# Modulo_Pisca_Vidros_SCH.net
KiCad netlist of a schematic drawn in Altium Designer
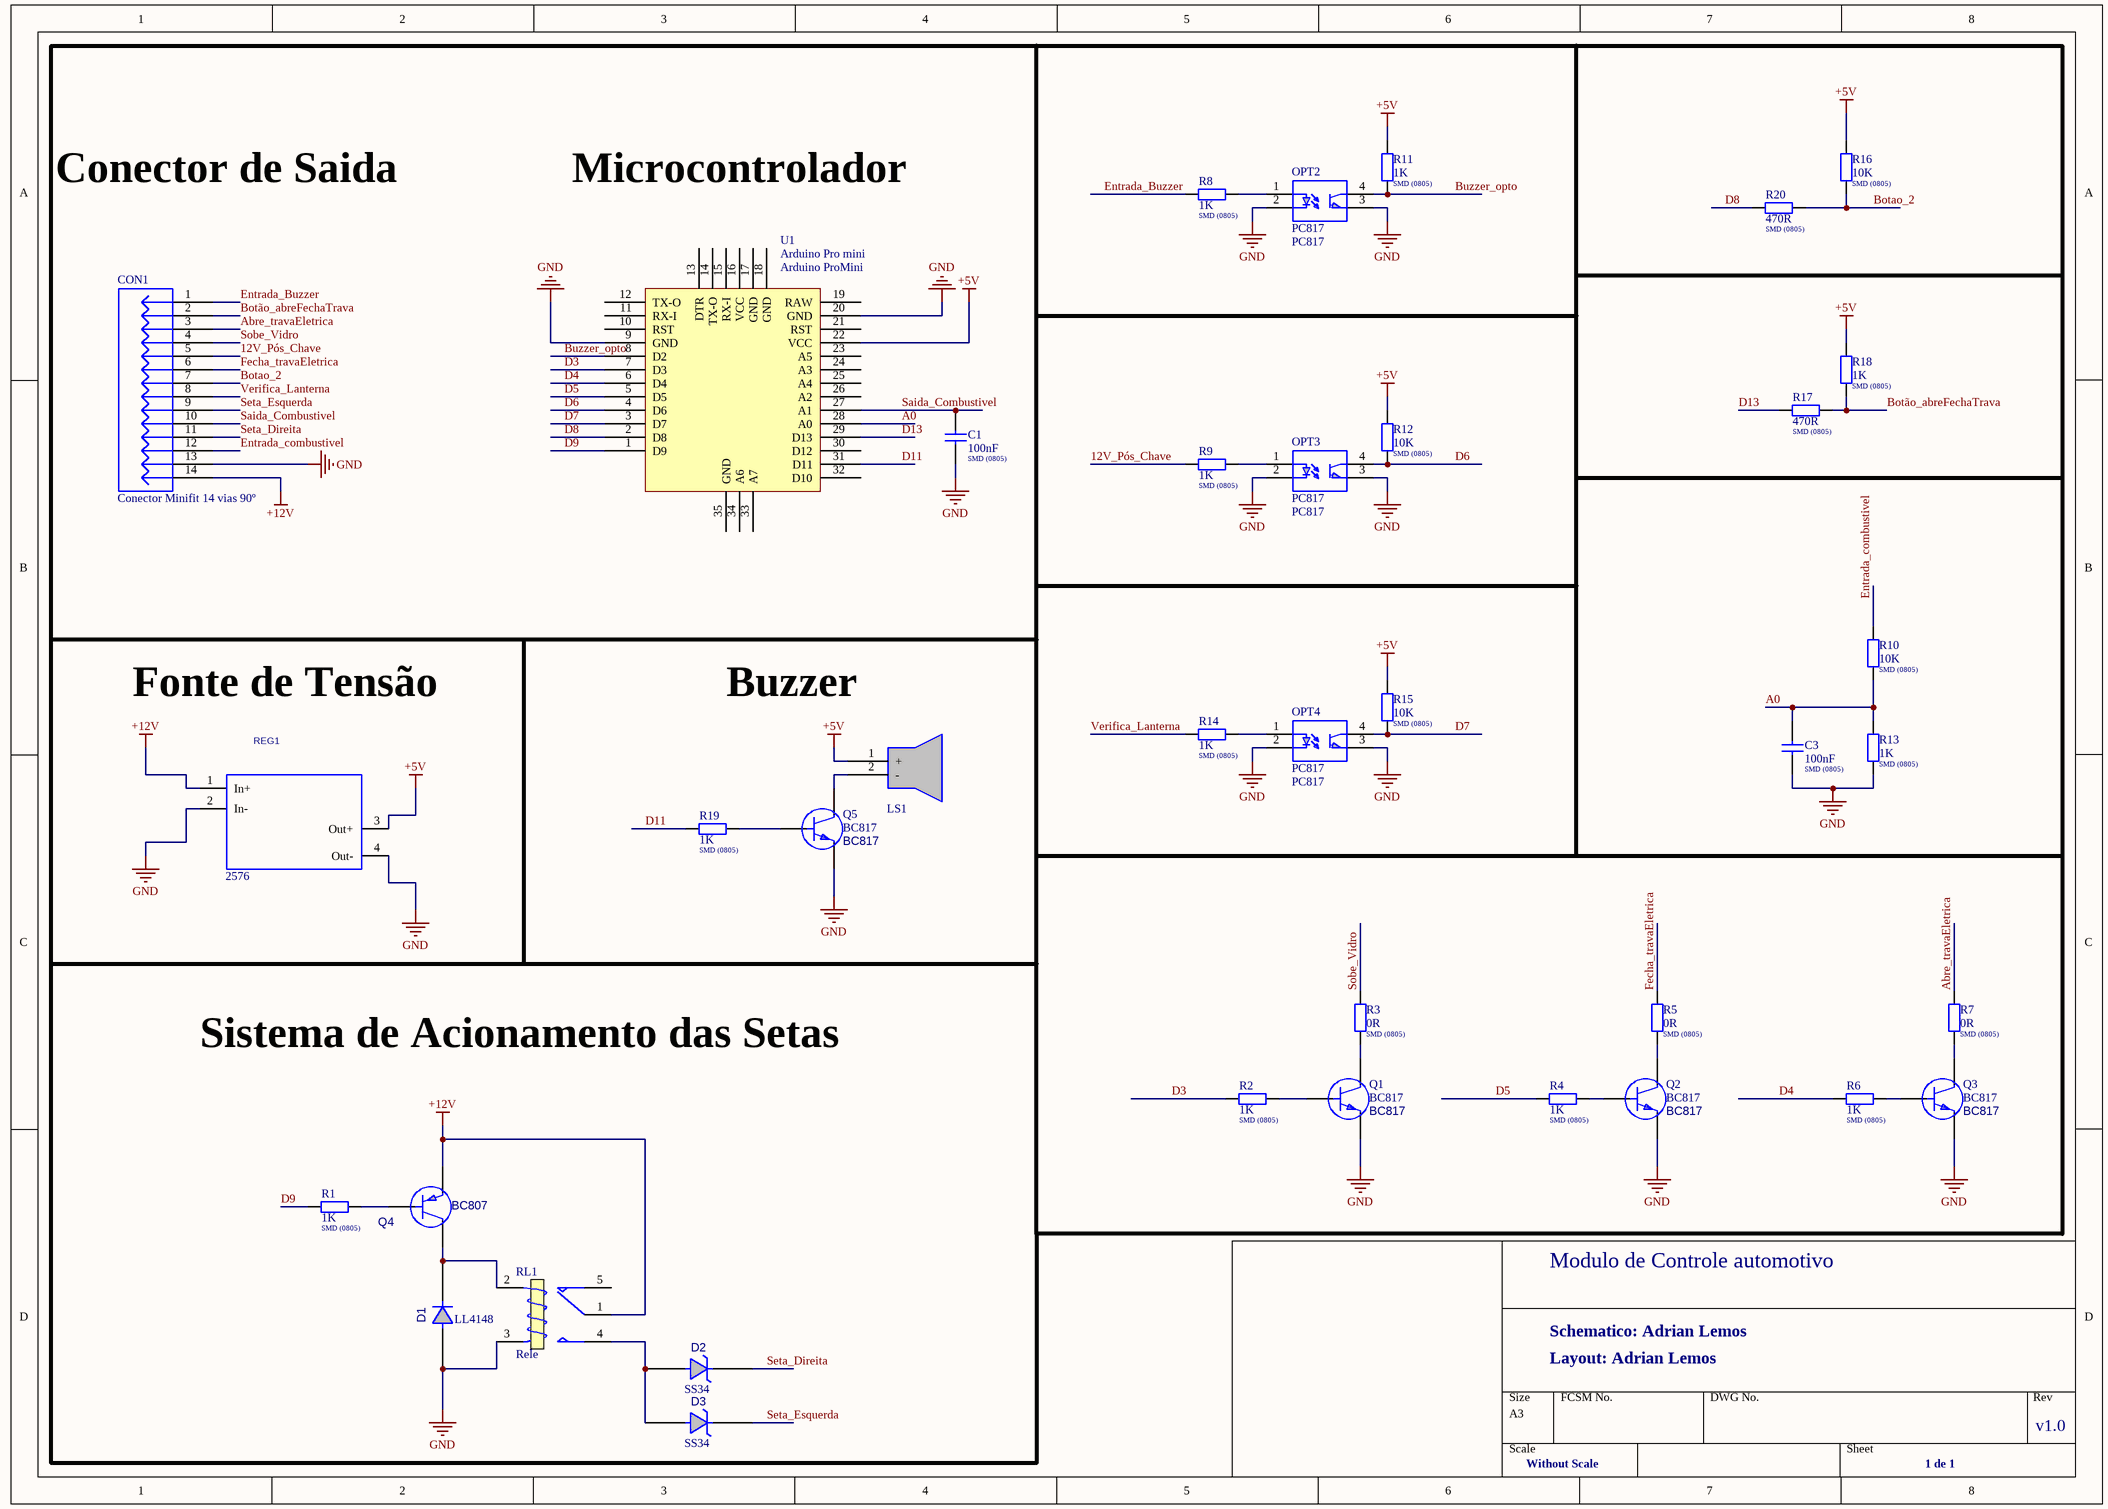
[diagram p0: Modulo_Pisca_Vidros_SCH.SchDoc]

(export (version "E")
  (design (tool "Eeschema 10.0.6"))
  (components
    (comp (ref "C1")
      (value "Capacitor SMD")
      (footprint "CAP_0805")
      (fields (field (name "VALOR") "100nF") (field (name "ENCAPSULAMENTO") "SMD (0805)"))
      (libsource (lib "Altium_Library_Brasil") (part "Capacitor SMD"))
    )
    (comp (ref "C3")
      (value "Capacitor SMD")
      (footprint "CAP_0805")
      (fields (field (name "VALOR") "100nF") (field (name "ENCAPSULAMENTO") "SMD (0805)"))
      (libsource (lib "Altium_Library_Brasil") (part "Capacitor SMD"))
    )
    (comp (ref "CON1")
      (value "Minifit_14vias_90º")
      (footprint "MFPL-14")
      (description "Minifit 14 vias 90º")
      (fields (field (name "DESCRI敲O") "Conector Minifit 14 vias 90º"))
      (libsource (lib "Altium_Library_Brasil") (part "Minifit_14vias_90º"))
    )
    (comp (ref "D1")
      (value "LL4148")
      (footprint "SOD80C MINIMELF")
      (description "Diodo LL4148 Melf")
      (fields (field (name "MODELO") "LL4148"))
      (libsource (lib "Altium_Library_Brasil") (part "LL4148"))
    )
    (comp (ref "D2")
      (value "SS34")
      (footprint "DO214AB")
      (description "DIODO-SCHOTTKY-SMD 3A 40V")
      (fields (field (name "MODELO") "SS34"))
      (libsource (lib "Altium_Library_Brasil") (part "SS34"))
    )
    (comp (ref "D3")
      (value "SS34")
      (footprint "DO214AB")
      (description "DIODO-SCHOTTKY-SMD 3A 40V")
      (fields (field (name "MODELO") "SS34"))
      (libsource (lib "Altium_Library_Brasil") (part "SS34"))
    )
    (comp (ref "LS1")
      (value "BUZZER")
      (footprint "Buzzer")
      (description "DC Buzzer")
      (libsource (lib "Altium_Library_Brasil") (part "BUZZER"))
    )
    (comp (ref "OPT2")
      (value "PC817")
      (footprint "DIP-4 SMD")
      (description "OptoAcoplador 4 terminais")
      (fields (field (name "MODELO") "PC817"))
      (libsource (lib "Altium_Library_Brasil") (part "PC817"))
    )
    (comp (ref "OPT3")
      (value "PC817")
      (footprint "DIP-4 SMD")
      (description "OptoAcoplador 4 terminais")
      (fields (field (name "MODELO") "PC817"))
      (libsource (lib "Altium_Library_Brasil") (part "PC817"))
    )
    (comp (ref "OPT4")
      (value "PC817")
      (footprint "DIP-4 SMD")
      (description "OptoAcoplador 4 terminais")
      (fields (field (name "MODELO") "PC817"))
      (libsource (lib "Altium_Library_Brasil") (part "PC817"))
    )
    (comp (ref "Q1")
      (value "BC817")
      (footprint "SOT23")
      (description "Transistor SMD NPN")
      (fields (field (name "MODELO") "BC817"))
      (libsource (lib "Altium_Library_Brasil") (part "BC817"))
    )
    (comp (ref "Q2")
      (value "BC817")
      (footprint "SOT23")
      (description "Transistor SMD NPN")
      (fields (field (name "MODELO") "BC817"))
      (libsource (lib "Altium_Library_Brasil") (part "BC817"))
    )
    (comp (ref "Q3")
      (value "BC817")
      (footprint "SOT23")
      (description "Transistor SMD NPN")
      (fields (field (name "MODELO") "BC817"))
      (libsource (lib "Altium_Library_Brasil") (part "BC817"))
    )
    (comp (ref "Q4")
      (value "BC807")
      (footprint "SOT23")
      (description "Transistor SMD PNP")
      (fields (field (name "MODELO") "BC807"))
      (libsource (lib "Altium_Library_Brasil") (part "BC807"))
    )
    (comp (ref "Q5")
      (value "BC817")
      (footprint "SOT23")
      (description "Transistor SMD NPN")
      (fields (field (name "MODELO") "BC817"))
      (libsource (lib "Altium_Library_Brasil") (part "BC817"))
    )
    (comp (ref "R1")
      (value "Resistor SMD")
      (footprint "RES_0805")
      (fields (field (name "VALOR") "1K") (field (name "ENCAPSULAMENTO") "SMD (0805)"))
      (libsource (lib "") (part "Resistor SMD_1"))
    )
    (comp (ref "R2")
      (value "Resistor SMD")
      (footprint "RES_0805")
      (fields (field (name "VALOR") "1K") (field (name "ENCAPSULAMENTO") "SMD (0805)"))
      (libsource (lib "") (part "Resistor SMD_1"))
    )
    (comp (ref "R3")
      (value "Resistor SMD")
      (footprint "RES_0805")
      (fields (field (name "VALOR") "0R") (field (name "ENCAPSULAMENTO") "SMD (0805)"))
      (libsource (lib "") (part "Resistor SMD_2"))
    )
    (comp (ref "R4")
      (value "Resistor SMD")
      (footprint "RES_0805")
      (fields (field (name "VALOR") "1K") (field (name "ENCAPSULAMENTO") "SMD (0805)"))
      (libsource (lib "") (part "Resistor SMD_1"))
    )
    (comp (ref "R5")
      (value "Resistor SMD")
      (footprint "RES_0805")
      (fields (field (name "VALOR") "0R") (field (name "ENCAPSULAMENTO") "SMD (0805)"))
      (libsource (lib "") (part "Resistor SMD_2"))
    )
    (comp (ref "R6")
      (value "Resistor SMD")
      (footprint "RES_0805")
      (fields (field (name "VALOR") "1K") (field (name "ENCAPSULAMENTO") "SMD (0805)"))
      (libsource (lib "") (part "Resistor SMD_1"))
    )
    (comp (ref "R7")
      (value "Resistor SMD")
      (footprint "RES_0805")
      (fields (field (name "VALOR") "0R") (field (name "ENCAPSULAMENTO") "SMD (0805)"))
      (libsource (lib "") (part "Resistor SMD_2"))
    )
    (comp (ref "R8")
      (value "Resistor SMD")
      (footprint "RES_0805")
      (fields (field (name "VALOR") "1K") (field (name "ENCAPSULAMENTO") "SMD (0805)"))
      (libsource (lib "Altium_Library_Brasil") (part "Resistor SMD"))
    )
    (comp (ref "R9")
      (value "Resistor SMD")
      (footprint "RES_0805")
      (fields (field (name "VALOR") "1K") (field (name "ENCAPSULAMENTO") "SMD (0805)"))
      (libsource (lib "Altium_Library_Brasil") (part "Resistor SMD"))
    )
    (comp (ref "R10")
      (value "Resistor SMD")
      (footprint "RES_0805")
      (fields (field (name "VALOR") "10K") (field (name "ENCAPSULAMENTO") "SMD (0805)"))
      (libsource (lib "") (part "Resistor SMD_2"))
    )
    (comp (ref "R11")
      (value "Resistor SMD")
      (footprint "RES_0805")
      (fields (field (name "VALOR") "1K") (field (name "ENCAPSULAMENTO") "SMD (0805)"))
      (libsource (lib "") (part "Resistor SMD_3"))
    )
    (comp (ref "R12")
      (value "Resistor SMD")
      (footprint "RES_0805")
      (fields (field (name "VALOR") "10K") (field (name "ENCAPSULAMENTO") "SMD (0805)"))
      (libsource (lib "") (part "Resistor SMD_3"))
    )
    (comp (ref "R13")
      (value "Resistor SMD")
      (footprint "RES_0805")
      (fields (field (name "VALOR") "1K") (field (name "ENCAPSULAMENTO") "SMD (0805)"))
      (libsource (lib "") (part "Resistor SMD_2"))
    )
    (comp (ref "R14")
      (value "Resistor SMD")
      (footprint "RES_0805")
      (fields (field (name "VALOR") "1K") (field (name "ENCAPSULAMENTO") "SMD (0805)"))
      (libsource (lib "Altium_Library_Brasil") (part "Resistor SMD"))
    )
    (comp (ref "R15")
      (value "Resistor SMD")
      (footprint "RES_0805")
      (fields (field (name "VALOR") "10K") (field (name "ENCAPSULAMENTO") "SMD (0805)"))
      (libsource (lib "") (part "Resistor SMD_3"))
    )
    (comp (ref "R16")
      (value "Resistor SMD")
      (footprint "RES_0805")
      (fields (field (name "VALOR") "10K") (field (name "ENCAPSULAMENTO") "SMD (0805)"))
      (libsource (lib "") (part "Resistor SMD_2"))
    )
    (comp (ref "R17")
      (value "Resistor SMD")
      (footprint "RES_0805")
      (fields (field (name "VALOR") "470R") (field (name "ENCAPSULAMENTO") "SMD (0805)"))
      (libsource (lib "Altium_Library_Brasil") (part "Resistor SMD"))
    )
    (comp (ref "R18")
      (value "Resistor SMD")
      (footprint "RES_0805")
      (fields (field (name "VALOR") "1K") (field (name "ENCAPSULAMENTO") "SMD (0805)"))
      (libsource (lib "") (part "Resistor SMD_2"))
    )
    (comp (ref "R19")
      (value "Resistor SMD")
      (footprint "RES_0805")
      (fields (field (name "VALOR") "1K") (field (name "ENCAPSULAMENTO") "SMD (0805)"))
      (libsource (lib "") (part "Resistor SMD_1"))
    )
    (comp (ref "R20")
      (value "Resistor SMD")
      (footprint "RES_0805")
      (fields (field (name "VALOR") "470R") (field (name "ENCAPSULAMENTO") "SMD (0805)"))
      (libsource (lib "") (part "Resistor SMD_1"))
    )
    (comp (ref "REG1")
      (value "voltage_regulator_module")
      (footprint "2576_Module")
      (description "Modulo Regulador de tensão 3A")
      (fields (field (name "MODELO") "2576"))
      (libsource (lib "AT_HTX_Lib") (part "voltage_regulator_module"))
    )
    (comp (ref "RL1")
      (value "Rele")
      (footprint "Rele MA1RC2 - Metaltex")
      (libsource (lib "Altium_Library_Brasil") (part "Rele NA/NF"))
    )
    (comp (ref "U1")
      (value "Arduino Pro mini")
      (footprint "Arduino Pro Mini")
      (fields (field (name "MODELO") "Arduino ProMini"))
      (libsource (lib "Altium_Library_Brasil") (part "Arduino Pro mini"))
    )
  )
  (nets
    (net (code "1") (name "+5V") (class "Default")
      (node (ref "LS1") (pin "1") (pinfunction "+_1") (pintype "passive"))
      (node (ref "R11") (pin "1") (pinfunction "1_1") (pintype "passive"))
      (node (ref "R12") (pin "1") (pinfunction "1_1") (pintype "passive"))
      (node (ref "R15") (pin "1") (pinfunction "1_1") (pintype "passive"))
      (node (ref "R16") (pin "2") (pinfunction "2_2") (pintype "passive"))
      (node (ref "R18") (pin "2") (pinfunction "2_2") (pintype "passive"))
      (node (ref "REG1") (pin "3") (pinfunction "Out+_3") (pintype "passive"))
      (node (ref "U1") (pin "22") (pinfunction "VCC_22") (pintype "passive"))
    )
    (net (code "2") (name "+12V") (class "Default")
      (node (ref "CON1") (pin "14") (pintype "passive"))
      (node (ref "Q4") (pin "2") (pinfunction "E_2") (pintype "passive"))
      (node (ref "REG1") (pin "1") (pinfunction "In+_1") (pintype "passive"))
      (node (ref "RL1") (pin "1") (pinfunction "COM_1") (pintype "passive"))
    )
    (net (code "3") (name "/12V_Pós_Chave") (class "Default")
      (node (ref "CON1") (pin "5") (pintype "passive"))
      (node (ref "R9") (pin "2") (pinfunction "2_2") (pintype "passive"))
    )
    (net (code "4") (name "/A0") (class "Default")
      (node (ref "C3") (pin "2") (pinfunction "2_2") (pintype "passive"))
      (node (ref "R10") (pin "1") (pinfunction "1_1") (pintype "passive"))
      (node (ref "R13") (pin "2") (pinfunction "2_2") (pintype "passive"))
      (node (ref "U1") (pin "28") (pinfunction "A0_28") (pintype "passive"))
    )
    (net (code "5") (name "/Abre_travaEletrica") (class "Default")
      (node (ref "CON1") (pin "3") (pintype "passive"))
      (node (ref "R7") (pin "2") (pinfunction "2_2") (pintype "passive"))
    )
    (net (code "6") (name "/Botao_2") (class "Default")
      (node (ref "CON1") (pin "7") (pintype "passive"))
      (node (ref "R16") (pin "1") (pinfunction "1_1") (pintype "passive"))
      (node (ref "R20") (pin "2") (pinfunction "2_2") (pintype "passive"))
    )
    (net (code "7") (name "/Botão_abreFechaTrava") (class "Default")
      (node (ref "CON1") (pin "2") (pintype "passive"))
      (node (ref "R17") (pin "1") (pinfunction "1_1") (pintype "passive"))
      (node (ref "R18") (pin "1") (pinfunction "1_1") (pintype "passive"))
    )
    (net (code "8") (name "/Buzzer_opto") (class "Default")
      (node (ref "OPT2") (pin "4") (pinfunction "COLETOR_4") (pintype "passive"))
      (node (ref "R11") (pin "2") (pinfunction "2_2") (pintype "passive"))
      (node (ref "U1") (pin "8") (pinfunction "D2_8") (pintype "passive"))
    )
    (net (code "9") (name "/D3") (class "Default")
      (node (ref "R2") (pin "1") (pinfunction "1_1") (pintype "passive"))
      (node (ref "U1") (pin "7") (pinfunction "D3_7") (pintype "passive"))
    )
    (net (code "10") (name "/D4") (class "Default")
      (node (ref "R6") (pin "1") (pinfunction "1_1") (pintype "passive"))
      (node (ref "U1") (pin "6") (pinfunction "D4_6") (pintype "passive"))
    )
    (net (code "11") (name "/D5") (class "Default")
      (node (ref "R4") (pin "1") (pinfunction "1_1") (pintype "passive"))
      (node (ref "U1") (pin "5") (pinfunction "D5_5") (pintype "passive"))
    )
    (net (code "12") (name "/D6") (class "Default")
      (node (ref "OPT3") (pin "4") (pinfunction "COLETOR_4") (pintype "passive"))
      (node (ref "R12") (pin "2") (pinfunction "2_2") (pintype "passive"))
      (node (ref "U1") (pin "4") (pinfunction "D6_4") (pintype "passive"))
    )
    (net (code "13") (name "/D7") (class "Default")
      (node (ref "OPT4") (pin "4") (pinfunction "COLETOR_4") (pintype "passive"))
      (node (ref "R15") (pin "2") (pinfunction "2_2") (pintype "passive"))
      (node (ref "U1") (pin "3") (pinfunction "D7_3") (pintype "passive"))
    )
    (net (code "14") (name "/D8") (class "Default")
      (node (ref "R20") (pin "1") (pinfunction "1_1") (pintype "passive"))
      (node (ref "U1") (pin "2") (pinfunction "D8_2") (pintype "passive"))
    )
    (net (code "15") (name "/D9") (class "Default")
      (node (ref "R1") (pin "1") (pinfunction "1_1") (pintype "passive"))
      (node (ref "U1") (pin "1") (pinfunction "D9_1") (pintype "passive"))
    )
    (net (code "16") (name "/D11") (class "Default")
      (node (ref "R19") (pin "1") (pinfunction "1_1") (pintype "passive"))
      (node (ref "U1") (pin "31") (pinfunction "D11_31") (pintype "passive"))
    )
    (net (code "17") (name "/D13") (class "Default")
      (node (ref "R17") (pin "2") (pinfunction "2_2") (pintype "passive"))
      (node (ref "U1") (pin "29") (pinfunction "D13_29") (pintype "passive"))
    )
    (net (code "18") (name "/Entrada_Buzzer") (class "Default")
      (node (ref "CON1") (pin "1") (pintype "passive"))
      (node (ref "R8") (pin "2") (pinfunction "2_2") (pintype "passive"))
    )
    (net (code "19") (name "/Entrada_combustivel") (class "Default")
      (node (ref "CON1") (pin "12") (pintype "passive"))
      (node (ref "R10") (pin "2") (pinfunction "2_2") (pintype "passive"))
    )
    (net (code "20") (name "/Fecha_travaEletrica") (class "Default")
      (node (ref "CON1") (pin "6") (pintype "passive"))
      (node (ref "R5") (pin "2") (pinfunction "2_2") (pintype "passive"))
    )
    (net (code "21") (name "/Saida_Combustivel") (class "Default")
      (node (ref "C1") (pin "1") (pinfunction "1_1") (pintype "passive"))
      (node (ref "CON1") (pin "10") (pintype "passive"))
      (node (ref "U1") (pin "27") (pinfunction "A1_27") (pintype "passive"))
    )
    (net (code "22") (name "/Seta_Direita") (class "Default")
      (node (ref "CON1") (pin "11") (pintype "passive"))
      (node (ref "D2") (pin "2") (pinfunction "2_2") (pintype "passive"))
    )
    (net (code "23") (name "/Seta_Esquerda") (class "Default")
      (node (ref "CON1") (pin "9") (pintype "passive"))
      (node (ref "D3") (pin "2") (pinfunction "2_2") (pintype "passive"))
    )
    (net (code "24") (name "/Sobe_Vidro") (class "Default")
      (node (ref "CON1") (pin "4") (pintype "passive"))
      (node (ref "R3") (pin "2") (pinfunction "2_2") (pintype "passive"))
    )
    (net (code "25") (name "/Verifica_Lanterna") (class "Default")
      (node (ref "CON1") (pin "8") (pintype "passive"))
      (node (ref "R14") (pin "2") (pinfunction "2_2") (pintype "passive"))
    )
    (net (code "26") (name "GND") (class "Default")
      (node (ref "C1") (pin "2") (pinfunction "2_2") (pintype "passive"))
      (node (ref "C3") (pin "1") (pinfunction "1_1") (pintype "passive"))
      (node (ref "CON1") (pin "13") (pintype "passive"))
      (node (ref "D1") (pin "2") (pinfunction "2_2") (pintype "passive"))
      (node (ref "OPT2") (pin "2") (pinfunction "K_2") (pintype "passive"))
      (node (ref "OPT2") (pin "3") (pinfunction "EMISSOR_3") (pintype "passive"))
      (node (ref "OPT3") (pin "2") (pinfunction "K_2") (pintype "passive"))
      (node (ref "OPT3") (pin "3") (pinfunction "EMISSOR_3") (pintype "passive"))
      (node (ref "OPT4") (pin "2") (pinfunction "K_2") (pintype "passive"))
      (node (ref "OPT4") (pin "3") (pinfunction "EMISSOR_3") (pintype "passive"))
      (node (ref "Q1") (pin "2") (pinfunction "E_2") (pintype "passive"))
      (node (ref "Q2") (pin "2") (pinfunction "E_2") (pintype "passive"))
      (node (ref "Q3") (pin "2") (pinfunction "E_2") (pintype "passive"))
      (node (ref "Q5") (pin "2") (pinfunction "E_2") (pintype "passive"))
      (node (ref "R13") (pin "1") (pinfunction "1_1") (pintype "passive"))
      (node (ref "REG1") (pin "2") (pinfunction "In-_2") (pintype "passive"))
      (node (ref "REG1") (pin "4") (pinfunction "Out-_4") (pintype "passive"))
      (node (ref "RL1") (pin "3") (pinfunction "T2_3") (pintype "passive"))
      (node (ref "U1") (pin "20") (pinfunction "GND_20") (pintype "passive"))
      (node (ref "U1") (pin "9") (pinfunction "GND_9") (pintype "passive"))
    )
    (net (code "27") (name "Net-(LS1--)") (class "Default")
      (node (ref "LS1") (pin "2") (pinfunction "-_2") (pintype "passive"))
      (node (ref "Q5") (pin "3") (pinfunction "C_3") (pintype "passive"))
    )
    (net (code "28") (name "Net-(OPT2-A)") (class "Default")
      (node (ref "OPT2") (pin "1") (pinfunction "A_1") (pintype "passive"))
      (node (ref "R8") (pin "1") (pinfunction "1_1") (pintype "passive"))
    )
    (net (code "29") (name "Net-(OPT3-A)") (class "Default")
      (node (ref "OPT3") (pin "1") (pinfunction "A_1") (pintype "passive"))
      (node (ref "R9") (pin "1") (pinfunction "1_1") (pintype "passive"))
    )
    (net (code "30") (name "Net-(OPT4-A)") (class "Default")
      (node (ref "OPT4") (pin "1") (pinfunction "A_1") (pintype "passive"))
      (node (ref "R14") (pin "1") (pinfunction "1_1") (pintype "passive"))
    )
    (net (code "31") (name "Net-(Q1-B)") (class "Default")
      (node (ref "Q1") (pin "1") (pinfunction "B_1") (pintype "passive"))
      (node (ref "R2") (pin "2") (pinfunction "2_2") (pintype "passive"))
    )
    (net (code "32") (name "Net-(Q1-C)") (class "Default")
      (node (ref "Q1") (pin "3") (pinfunction "C_3") (pintype "passive"))
      (node (ref "R3") (pin "1") (pinfunction "1_1") (pintype "passive"))
    )
    (net (code "33") (name "Net-(Q2-B)") (class "Default")
      (node (ref "Q2") (pin "1") (pinfunction "B_1") (pintype "passive"))
      (node (ref "R4") (pin "2") (pinfunction "2_2") (pintype "passive"))
    )
    (net (code "34") (name "Net-(Q2-C)") (class "Default")
      (node (ref "Q2") (pin "3") (pinfunction "C_3") (pintype "passive"))
      (node (ref "R5") (pin "1") (pinfunction "1_1") (pintype "passive"))
    )
    (net (code "35") (name "Net-(Q3-B)") (class "Default")
      (node (ref "Q3") (pin "1") (pinfunction "B_1") (pintype "passive"))
      (node (ref "R6") (pin "2") (pinfunction "2_2") (pintype "passive"))
    )
    (net (code "36") (name "Net-(Q3-C)") (class "Default")
      (node (ref "Q3") (pin "3") (pinfunction "C_3") (pintype "passive"))
      (node (ref "R7") (pin "1") (pinfunction "1_1") (pintype "passive"))
    )
    (net (code "37") (name "Net-(Q4-B)") (class "Default")
      (node (ref "Q4") (pin "1") (pinfunction "B_1") (pintype "passive"))
      (node (ref "R1") (pin "2") (pinfunction "2_2") (pintype "passive"))
    )
    (net (code "38") (name "Net-(Q4-C)") (class "Default")
      (node (ref "D1") (pin "1") (pinfunction "1_1") (pintype "passive"))
      (node (ref "Q4") (pin "3") (pinfunction "C_3") (pintype "passive"))
      (node (ref "RL1") (pin "2") (pinfunction "T1_2") (pintype "passive"))
    )
    (net (code "39") (name "Net-(Q5-B)") (class "Default")
      (node (ref "Q5") (pin "1") (pinfunction "B_1") (pintype "passive"))
      (node (ref "R19") (pin "2") (pinfunction "2_2") (pintype "passive"))
    )
    (net (code "40") (name "Net-(RL1-NO)") (class "Default")
      (node (ref "D2") (pin "1") (pinfunction "1_1") (pintype "passive"))
      (node (ref "D3") (pin "1") (pinfunction "1_1") (pintype "passive"))
      (node (ref "RL1") (pin "4") (pinfunction "NO_4") (pintype "passive"))
    )
    (net (code "41") (name "unconnected-(RL1-NC-Pad5)") (class "Default")
      (node (ref "RL1") (pin "5") (pinfunction "NC_5") (pintype "passive"))
    )
    (net (code "42") (name "unconnected-(U1-A2-Pad26)") (class "Default")
      (node (ref "U1") (pin "26") (pinfunction "A2_26") (pintype "passive"))
    )
    (net (code "43") (name "unconnected-(U1-A3-Pad24)") (class "Default")
      (node (ref "U1") (pin "24") (pinfunction "A3_24") (pintype "passive"))
    )
    (net (code "44") (name "unconnected-(U1-A4-Pad25)") (class "Default")
      (node (ref "U1") (pin "25") (pinfunction "A4_25") (pintype "passive"))
    )
    (net (code "45") (name "unconnected-(U1-A5-Pad23)") (class "Default")
      (node (ref "U1") (pin "23") (pinfunction "A5_23") (pintype "passive"))
    )
    (net (code "46") (name "unconnected-(U1-A6-Pad34)") (class "Default")
      (node (ref "U1") (pin "34") (pinfunction "A6_34") (pintype "passive"))
    )
    (net (code "47") (name "unconnected-(U1-A7-Pad33)") (class "Default")
      (node (ref "U1") (pin "33") (pinfunction "A7_33") (pintype "passive"))
    )
    (net (code "48") (name "unconnected-(U1-D10-Pad32)") (class "Default")
      (node (ref "U1") (pin "32") (pinfunction "D10_32") (pintype "passive"))
    )
    (net (code "49") (name "unconnected-(U1-D12-Pad30)") (class "Default")
      (node (ref "U1") (pin "30") (pinfunction "D12_30") (pintype "passive"))
    )
    (net (code "50") (name "unconnected-(U1-DTR-Pad13)") (class "Default")
      (node (ref "U1") (pin "13") (pinfunction "DTR_13") (pintype "passive"))
    )
    (net (code "51") (name "unconnected-(U1-GND-Pad17)") (class "Default")
      (node (ref "U1") (pin "17") (pinfunction "GND_17") (pintype "passive"))
    )
    (net (code "52") (name "unconnected-(U1-GND-Pad18)") (class "Default")
      (node (ref "U1") (pin "18") (pinfunction "GND_18") (pintype "passive"))
    )
    (net (code "53") (name "unconnected-(U1-GND-Pad35)") (class "Default")
      (node (ref "U1") (pin "35") (pinfunction "GND_35") (pintype "passive"))
    )
    (net (code "54") (name "unconnected-(U1-RAW-Pad19)") (class "Default")
      (node (ref "U1") (pin "19") (pinfunction "RAW_19") (pintype "passive"))
    )
    (net (code "55") (name "unconnected-(U1-RST-Pad10)") (class "Default")
      (node (ref "U1") (pin "10") (pinfunction "RST_10") (pintype "passive"))
    )
    (net (code "56") (name "unconnected-(U1-RST-Pad21)") (class "Default")
      (node (ref "U1") (pin "21") (pinfunction "RST_21") (pintype "passive"))
    )
    (net (code "57") (name "unconnected-(U1-RX-I-Pad11)") (class "Default")
      (node (ref "U1") (pin "11") (pinfunction "RX-I_11") (pintype "passive"))
    )
    (net (code "58") (name "unconnected-(U1-RX-I-Pad15)") (class "Default")
      (node (ref "U1") (pin "15") (pinfunction "RX-I_15") (pintype "passive"))
    )
    (net (code "59") (name "unconnected-(U1-TX-O-Pad12)") (class "Default")
      (node (ref "U1") (pin "12") (pinfunction "TX-O_12") (pintype "passive"))
    )
    (net (code "60") (name "unconnected-(U1-TX-O-Pad14)") (class "Default")
      (node (ref "U1") (pin "14") (pinfunction "TX-O_14") (pintype "passive"))
    )
    (net (code "61") (name "unconnected-(U1-VCC-Pad16)") (class "Default")
      (node (ref "U1") (pin "16") (pinfunction "VCC_16") (pintype "passive"))
    )
  )
)
